# bristol_longshot.net
KiCad netlist of a schematic drawn in EAGLE
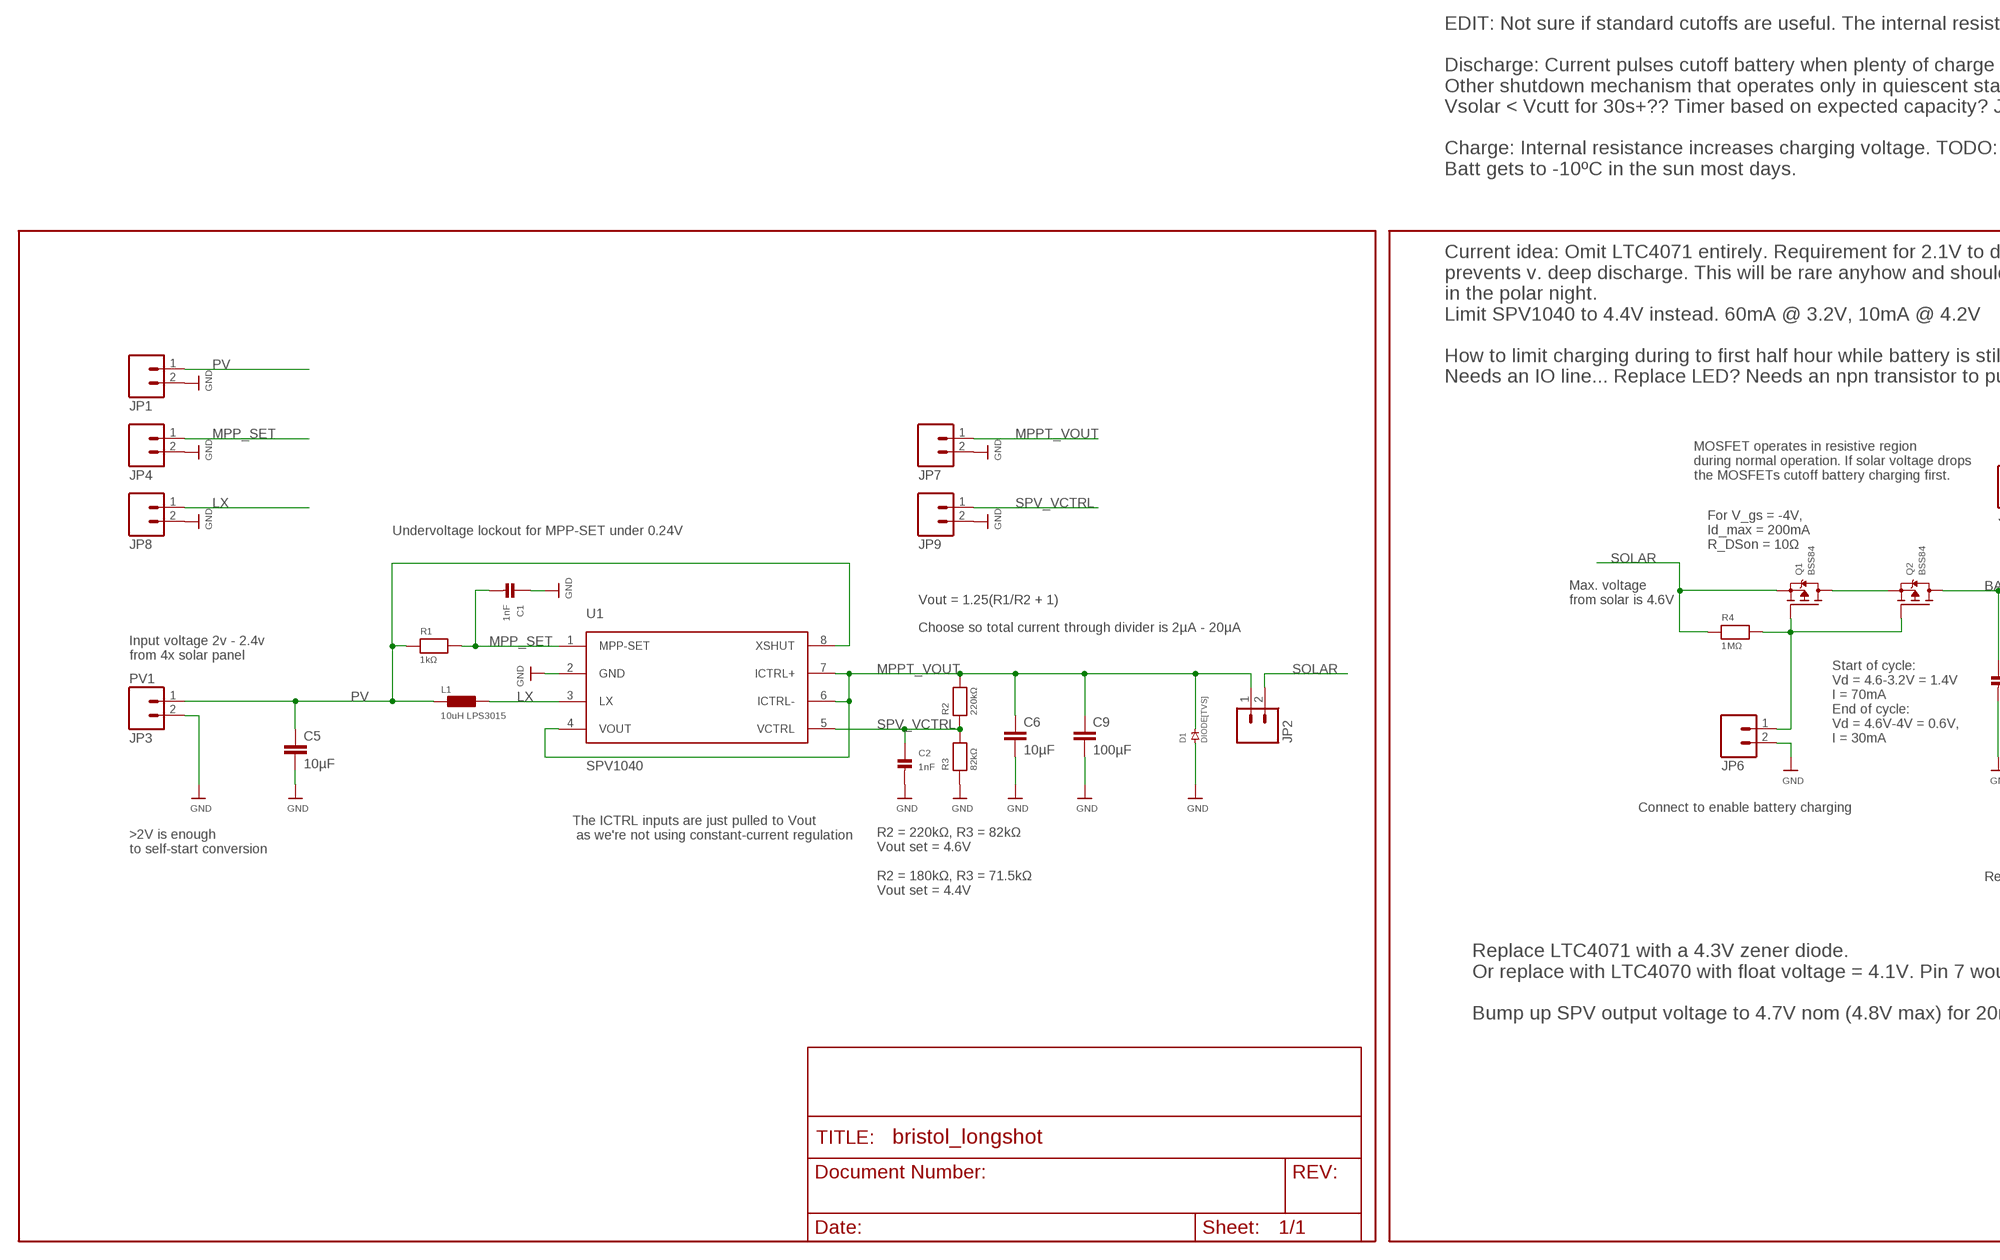
[diagram p0: schematic, sheet 1, part 1 of 2]
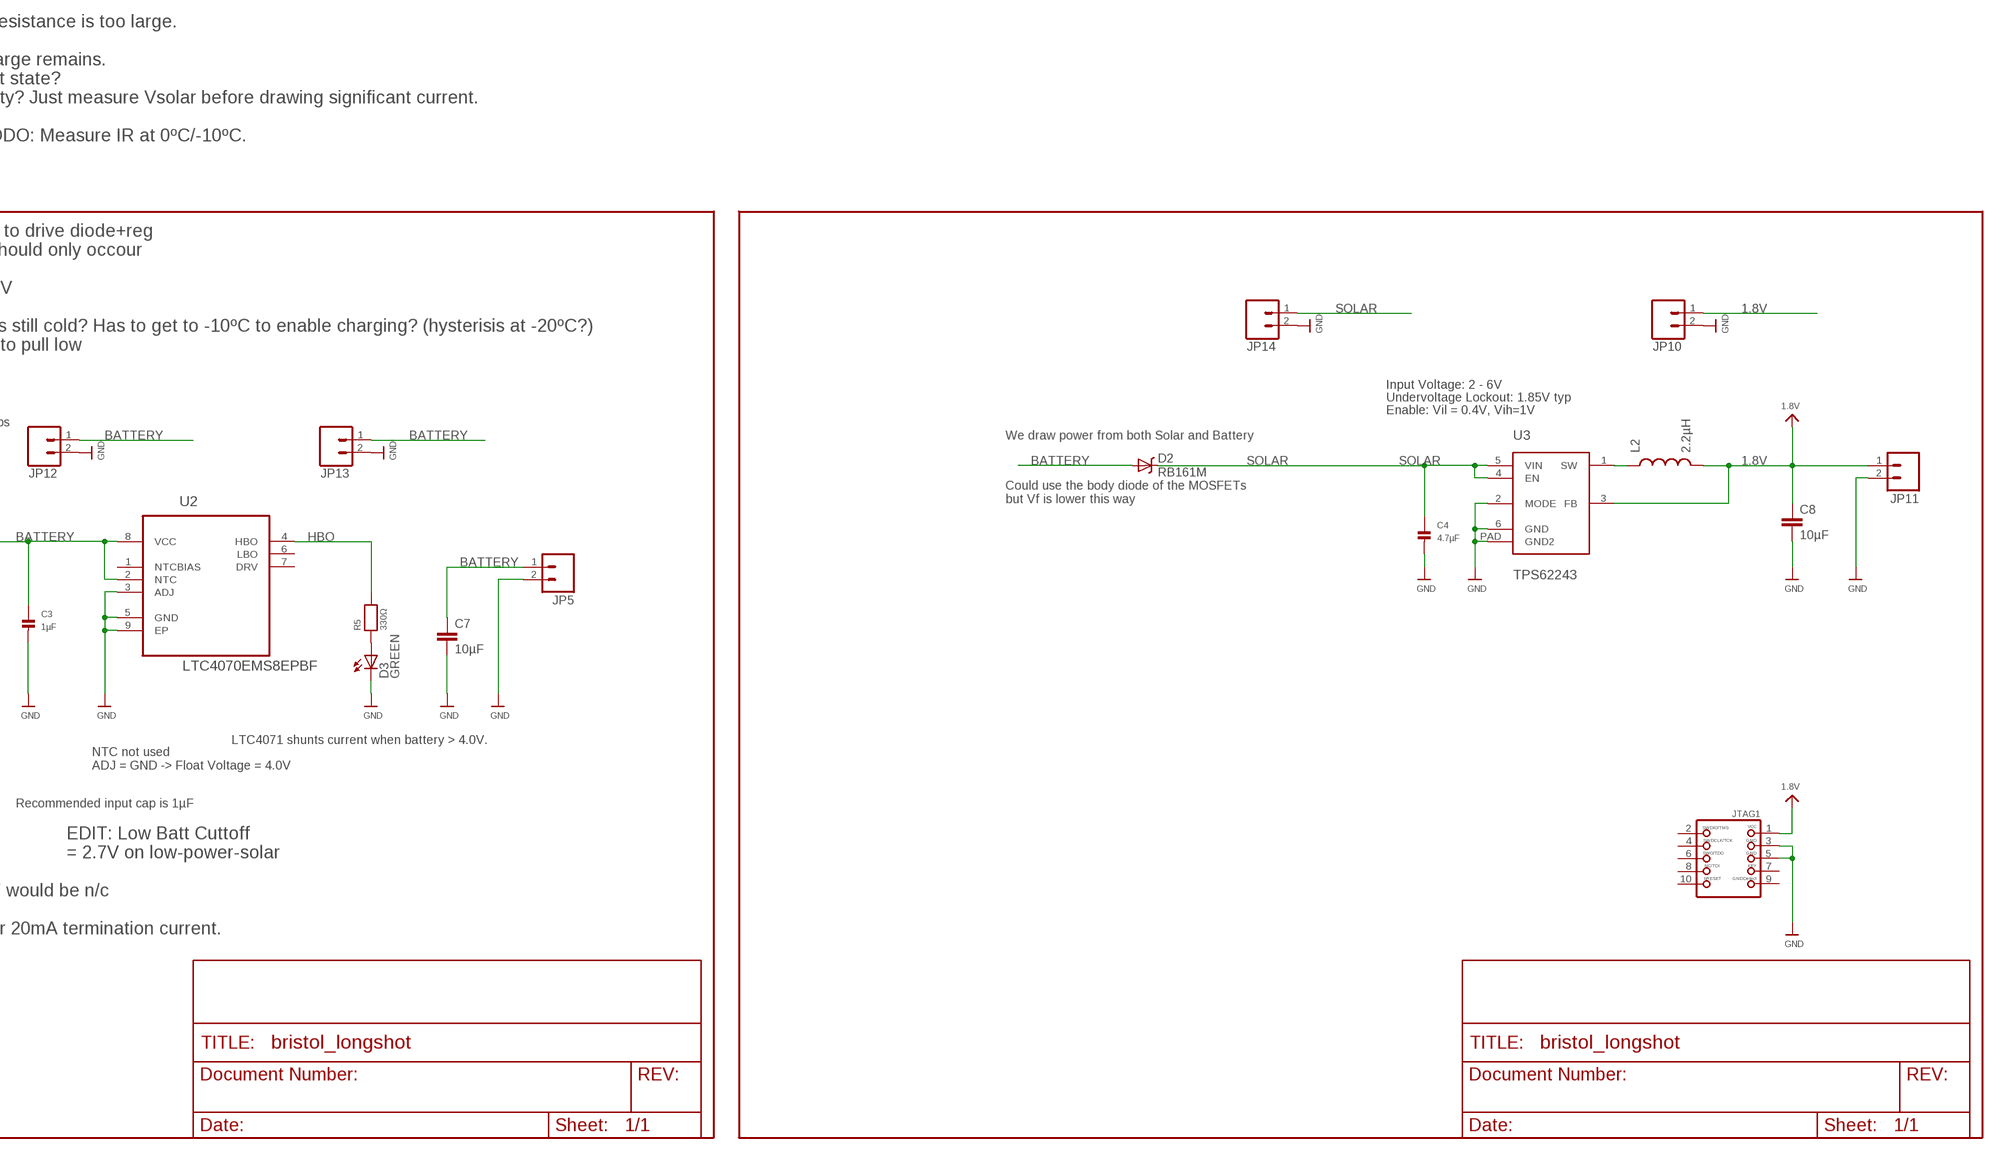
[diagram p1: schematic, sheet 1, part 2 of 2]

(export (version "E")
  (design (tool "Eeschema 10.0.6"))
  (components
    (comp (ref "C1")
      (value "1nF")
      (footprint "eagle-import:_0402@1")
      (libsource (lib "eagle-import") (part "CAP_CERAMIC_0402"))
    )
    (comp (ref "C2")
      (value "1nF")
      (footprint "eagle-import:_0402@1")
      (libsource (lib "eagle-import") (part "CAP_CERAMIC_0402"))
    )
    (comp (ref "C3")
      (value "1µF")
      (footprint "eagle-import:_0402@1")
      (libsource (lib "eagle-import") (part "CAP_CERAMIC_0402"))
    )
    (comp (ref "C4")
      (value "4.7µF")
      (footprint "eagle-import:_0402@1")
      (libsource (lib "eagle-import") (part "CAP_CERAMIC_0402"))
    )
    (comp (ref "C5")
      (value "10µF")
      (footprint "eagle-import:C0603K")
      (libsource (lib "eagle-import") (part "C-EUC0603K"))
    )
    (comp (ref "C6")
      (value "10µF")
      (footprint "eagle-import:C0603K")
      (libsource (lib "eagle-import") (part "C-EUC0603K"))
    )
    (comp (ref "C7")
      (value "10µF")
      (footprint "eagle-import:C0603K")
      (libsource (lib "eagle-import") (part "C-EUC0603K"))
    )
    (comp (ref "C8")
      (value "10µF")
      (footprint "eagle-import:C0603K")
      (libsource (lib "eagle-import") (part "C-EUC0603K"))
    )
    (comp (ref "C9")
      (value "100µF")
      (footprint "eagle-import:C1206K")
      (libsource (lib "eagle-import") (part "C-EUC1206K"))
    )
    (comp (ref "D1")
      (value "DIODE[TVS]")
      (footprint "eagle-import:SOD123W")
      (libsource (lib "eagle-import") (part "DIODE[TVS]"))
    )
    (comp (ref "D2")
      (value "RB161M")
      (footprint "eagle-import:RB161M")
      (libsource (lib "eagle-import") (part "RB161M"))
    )
    (comp (ref "D3")
      (value "GREEN")
      (footprint "eagle-import:CHIPLED_0603")
      (libsource (lib "eagle-import") (part "LEDCHIPLED_0603"))
    )
    (comp (ref "JP1")
      (value "M02LOCK")
      (footprint "eagle-import:1X02_LOCK")
      (libsource (lib "eagle-import") (part "M02LOCK"))
    )
    (comp (ref "JP2")
      (value "M02LOCK")
      (footprint "eagle-import:1X02_LOCK")
      (libsource (lib "eagle-import") (part "M02LOCK"))
    )
    (comp (ref "JP3")
      (value "PV1")
      (footprint "eagle-import:SCREWTERMINAL-3.5MM-2_LOCK")
      (libsource (lib "eagle-import") (part "M023.5MM_LOCK"))
    )
    (comp (ref "JP4")
      (value "M02LOCK")
      (footprint "eagle-import:1X02_LOCK")
      (libsource (lib "eagle-import") (part "M02LOCK"))
    )
    (comp (ref "JP5")
      (value "M023.5MM_LOCK")
      (footprint "eagle-import:SCREWTERMINAL-3.5MM-2_LOCK")
      (libsource (lib "eagle-import") (part "M023.5MM_LOCK"))
    )
    (comp (ref "JP6")
      (value "M02LOCK")
      (footprint "eagle-import:1X02_LOCK")
      (libsource (lib "eagle-import") (part "M02LOCK"))
    )
    (comp (ref "JP7")
      (value "M02LOCK")
      (footprint "eagle-import:1X02_LOCK")
      (libsource (lib "eagle-import") (part "M02LOCK"))
    )
    (comp (ref "JP8")
      (value "M02LOCK")
      (footprint "eagle-import:1X02_LOCK")
      (libsource (lib "eagle-import") (part "M02LOCK"))
    )
    (comp (ref "JP9")
      (value "M02LOCK")
      (footprint "eagle-import:1X02_LOCK")
      (libsource (lib "eagle-import") (part "M02LOCK"))
    )
    (comp (ref "JP10")
      (value "M02LOCK")
      (footprint "eagle-import:1X02_LOCK")
      (libsource (lib "eagle-import") (part "M02LOCK"))
    )
    (comp (ref "JP11")
      (value "M023.5MM_LOCK")
      (footprint "eagle-import:SCREWTERMINAL-3.5MM-2_LOCK")
      (libsource (lib "eagle-import") (part "M023.5MM_LOCK"))
    )
    (comp (ref "JP12")
      (value "M02LOCK")
      (footprint "eagle-import:1X02_LOCK")
      (libsource (lib "eagle-import") (part "M02LOCK"))
    )
    (comp (ref "JP13")
      (value "M02LOCK")
      (footprint "eagle-import:1X02_LOCK")
      (libsource (lib "eagle-import") (part "M02LOCK"))
    )
    (comp (ref "JP14")
      (value "M02LOCK")
      (footprint "eagle-import:1X02_LOCK")
      (libsource (lib "eagle-import") (part "M02LOCK"))
    )
    (comp (ref "JTAG1")
      (value "JTAG-CORTEXM3SMT")
      (footprint "eagle-import:2X05_1.27MM_SMT")
      (libsource (lib "eagle-import") (part "JTAG-CORTEXM3SMT"))
    )
    (comp (ref "L1")
      (value "10uH LPS3015")
      (footprint "eagle-import:LPS3015")
      (libsource (lib "eagle-import") (part "IND-LPS3015"))
    )
    (comp (ref "L2")
      (value "2.2µH")
      (footprint "eagle-import:1007")
      (libsource (lib "eagle-import") (part "INDUCTOR1007"))
    )
    (comp (ref "Q1")
      (value "BSS84")
      (footprint "eagle-import:SOT23")
      (libsource (lib "eagle-import") (part "NX2301P"))
    )
    (comp (ref "Q2")
      (value "BSS84")
      (footprint "eagle-import:SOT23")
      (libsource (lib "eagle-import") (part "NX2301P"))
    )
    (comp (ref "R1")
      (value "1kΩ")
      (footprint "eagle-import:_0402")
      (libsource (lib "eagle-import") (part "RESISTOR_0402"))
    )
    (comp (ref "R2")
      (value "220kΩ")
      (footprint "eagle-import:_0402")
      (libsource (lib "eagle-import") (part "RESISTOR_0402"))
    )
    (comp (ref "R3")
      (value "82kΩ")
      (footprint "eagle-import:_0402")
      (libsource (lib "eagle-import") (part "RESISTOR_0402"))
    )
    (comp (ref "R4")
      (value "1MΩ")
      (footprint "eagle-import:_0402")
      (libsource (lib "eagle-import") (part "RESISTOR_0402"))
    )
    (comp (ref "R5")
      (value "330Ω")
      (footprint "eagle-import:_0402")
      (libsource (lib "eagle-import") (part "RESISTOR_0402"))
    )
    (comp (ref "U1")
      (value "SPV1040")
      (footprint "eagle-import:TSSOP8")
      (libsource (lib "eagle-import") (part "SPV1040"))
    )
    (comp (ref "U2")
      (value "LTC4070EMS8EPBF")
      (footprint "eagle-import:SOP65P490X110-9N")
      (fields (field (name "MPN") "LTC4070EMS8E#PBF"))
      (libsource (lib "eagle-import") (part "LTC4070EMS8EPBF"))
    )
    (comp (ref "U3")
      (value "TPS62243")
      (footprint "eagle-import:S-PWSON-N6")
      (libsource (lib "eagle-import") (part "TPS62243"))
    )
  )
  (nets
    (net (code "1") (name "/BATTERY") (class "Default")
      (node (ref "C3") (pin "1") (pinfunction "P$1_1") (pintype "passive"))
      (node (ref "C7") (pin "1") (pinfunction "1_1") (pintype "passive"))
      (node (ref "D2") (pin "ANODE") (pinfunction "A_ANODE") (pintype "passive"))
      (node (ref "JP12") (pin "1") (pinfunction "1_1") (pintype "passive"))
      (node (ref "JP13") (pin "1") (pinfunction "1_1") (pintype "passive"))
      (node (ref "JP5") (pin "1") (pinfunction "1_1") (pintype "passive"))
      (node (ref "Q2") (pin "3") (pinfunction "D_3") (pintype "passive"))
      (node (ref "U2") (pin "2") (pinfunction "NTC_2") (pintype "input"))
      (node (ref "U2") (pin "8") (pinfunction "VCC_8") (pintype "power_in"))
    )
    (net (code "2") (name "/HBO") (class "Default")
      (node (ref "R5") (pin "2") (pinfunction "2_2") (pintype "passive"))
      (node (ref "U2") (pin "4") (pinfunction "HBO_4") (pintype "output"))
    )
    (net (code "3") (name "/LX") (class "Default")
      (node (ref "JP8") (pin "1") (pinfunction "1_1") (pintype "passive"))
      (node (ref "L1") (pin "2_1") (pinfunction "2_2_1") (pintype "passive"))
      (node (ref "L1") (pin "2_2") (pinfunction "2_2_2") (pintype "passive"))
      (node (ref "L1") (pin "2_3") (pinfunction "2_2_3") (pintype "passive"))
      (node (ref "L1") (pin "2_4") (pinfunction "2_2_4") (pintype "passive"))
      (node (ref "L1") (pin "2_5") (pinfunction "2_2_5") (pintype "passive"))
      (node (ref "L1") (pin "2_6") (pinfunction "2_2_6") (pintype "passive"))
      (node (ref "L1") (pin "2_7") (pinfunction "2_2_7") (pintype "passive"))
      (node (ref "L1") (pin "2_8") (pinfunction "2_2_8") (pintype "passive"))
      (node (ref "L1") (pin "2_9") (pinfunction "2_2_9") (pintype "passive"))
      (node (ref "U1") (pin "3") (pinfunction "LX_3") (pintype "bidirectional"))
    )
    (net (code "4") (name "/MPPT_VOUT") (class "Default")
      (node (ref "C6") (pin "1") (pinfunction "1_1") (pintype "passive"))
      (node (ref "C9") (pin "1") (pinfunction "1_1") (pintype "passive"))
      (node (ref "D1") (pin "P$2") (pinfunction "2_P$2") (pintype "bidirectional"))
      (node (ref "JP2") (pin "1") (pinfunction "1_1") (pintype "passive"))
      (node (ref "JP7") (pin "1") (pinfunction "1_1") (pintype "passive"))
      (node (ref "R2") (pin "2") (pinfunction "2_2") (pintype "passive"))
      (node (ref "U1") (pin "4") (pinfunction "VOUT_4") (pintype "bidirectional"))
      (node (ref "U1") (pin "6") (pinfunction "ICTRL-_6") (pintype "bidirectional"))
      (node (ref "U1") (pin "7") (pinfunction "ICTRL+_7") (pintype "bidirectional"))
    )
    (net (code "5") (name "/MPP_SET") (class "Default")
      (node (ref "C1") (pin "2") (pinfunction "P$2_2") (pintype "passive"))
      (node (ref "JP4") (pin "1") (pinfunction "1_1") (pintype "passive"))
      (node (ref "R1") (pin "2") (pinfunction "2_2") (pintype "passive"))
      (node (ref "U1") (pin "1") (pinfunction "MPP-SET_1") (pintype "bidirectional"))
    )
    (net (code "6") (name "/NTCBIAS") (class "Default")
      (node (ref "U2") (pin "1") (pinfunction "NTCBIAS_1") (pintype "power_in"))
    )
    (net (code "7") (name "/PV") (class "Default")
      (node (ref "C5") (pin "1") (pinfunction "1_1") (pintype "passive"))
      (node (ref "JP1") (pin "1") (pinfunction "1_1") (pintype "passive"))
      (node (ref "JP3") (pin "1") (pinfunction "1_1") (pintype "passive"))
      (node (ref "L1") (pin "1_1") (pinfunction "1_1_1") (pintype "passive"))
      (node (ref "L1") (pin "1_2") (pinfunction "1_1_2") (pintype "passive"))
      (node (ref "L1") (pin "1_3") (pinfunction "1_1_3") (pintype "passive"))
      (node (ref "L1") (pin "1_4") (pinfunction "1_1_4") (pintype "passive"))
      (node (ref "L1") (pin "1_5") (pinfunction "1_1_5") (pintype "passive"))
      (node (ref "L1") (pin "1_6") (pinfunction "1_1_6") (pintype "passive"))
      (node (ref "L1") (pin "1_7") (pinfunction "1_1_7") (pintype "passive"))
      (node (ref "L1") (pin "1_8") (pinfunction "1_1_8") (pintype "passive"))
      (node (ref "L1") (pin "1_9") (pinfunction "1_1_9") (pintype "passive"))
      (node (ref "R1") (pin "1") (pinfunction "1_1") (pintype "passive"))
      (node (ref "U1") (pin "8") (pinfunction "XSHUT_8") (pintype "bidirectional"))
    )
    (net (code "8") (name "/SOLAR") (class "Default")
      (node (ref "C4") (pin "1") (pinfunction "P$1_1") (pintype "passive"))
      (node (ref "D2") (pin "CATHODE") (pinfunction "C_CATHODE") (pintype "passive"))
      (node (ref "JP14") (pin "1") (pinfunction "1_1") (pintype "passive"))
      (node (ref "JP2") (pin "2") (pinfunction "2_2") (pintype "passive"))
      (node (ref "Q1") (pin "2") (pinfunction "S_2") (pintype "passive"))
      (node (ref "R4") (pin "1") (pinfunction "1_1") (pintype "passive"))
      (node (ref "U3") (pin "4") (pinfunction "EN_4") (pintype "bidirectional"))
      (node (ref "U3") (pin "5") (pinfunction "VIN_5") (pintype "bidirectional"))
    )
    (net (code "9") (name "/SPV_VCTRL") (class "Default")
      (node (ref "C2") (pin "1") (pinfunction "P$1_1") (pintype "passive"))
      (node (ref "JP9") (pin "1") (pinfunction "1_1") (pintype "passive"))
      (node (ref "R2") (pin "1") (pinfunction "1_1") (pintype "passive"))
      (node (ref "R3") (pin "2") (pinfunction "2_2") (pintype "passive"))
      (node (ref "U1") (pin "5") (pinfunction "VCTRL_5") (pintype "bidirectional"))
    )
    (net (code "10") (name "1.8V") (class "Default")
      (node (ref "C8") (pin "1") (pinfunction "1_1") (pintype "passive"))
      (node (ref "JP10") (pin "1") (pinfunction "1_1") (pintype "passive"))
      (node (ref "JP11") (pin "1") (pinfunction "1_1") (pintype "passive"))
      (node (ref "JTAG1") (pin "1") (pinfunction "1_1") (pintype "passive"))
      (node (ref "L2") (pin "2") (pinfunction "2_2") (pintype "passive"))
      (node (ref "U3") (pin "3") (pinfunction "FB_3") (pintype "bidirectional"))
    )
    (net (code "11") (name "GND") (class "Default")
      (node (ref "C1") (pin "1") (pinfunction "P$1_1") (pintype "passive"))
      (node (ref "C2") (pin "2") (pinfunction "P$2_2") (pintype "passive"))
      (node (ref "C3") (pin "2") (pinfunction "P$2_2") (pintype "passive"))
      (node (ref "C4") (pin "2") (pinfunction "P$2_2") (pintype "passive"))
      (node (ref "C5") (pin "2") (pinfunction "2_2") (pintype "passive"))
      (node (ref "C6") (pin "2") (pinfunction "2_2") (pintype "passive"))
      (node (ref "C7") (pin "2") (pinfunction "2_2") (pintype "passive"))
      (node (ref "C8") (pin "2") (pinfunction "2_2") (pintype "passive"))
      (node (ref "C9") (pin "2") (pinfunction "2_2") (pintype "passive"))
      (node (ref "D1") (pin "P$1") (pinfunction "1_P$1") (pintype "bidirectional"))
      (node (ref "D3") (pin "C") (pinfunction "C_C") (pintype "passive"))
      (node (ref "JP1") (pin "2") (pinfunction "2_2") (pintype "passive"))
      (node (ref "JP10") (pin "2") (pinfunction "2_2") (pintype "passive"))
      (node (ref "JP11") (pin "2") (pinfunction "2_2") (pintype "passive"))
      (node (ref "JP12") (pin "2") (pinfunction "2_2") (pintype "passive"))
      (node (ref "JP13") (pin "2") (pinfunction "2_2") (pintype "passive"))
      (node (ref "JP14") (pin "2") (pinfunction "2_2") (pintype "passive"))
      (node (ref "JP3") (pin "2") (pinfunction "2_2") (pintype "passive"))
      (node (ref "JP4") (pin "2") (pinfunction "2_2") (pintype "passive"))
      (node (ref "JP5") (pin "2") (pinfunction "2_2") (pintype "passive"))
      (node (ref "JP6") (pin "2") (pinfunction "2_2") (pintype "passive"))
      (node (ref "JP7") (pin "2") (pinfunction "2_2") (pintype "passive"))
      (node (ref "JP8") (pin "2") (pinfunction "2_2") (pintype "passive"))
      (node (ref "JP9") (pin "2") (pinfunction "2_2") (pintype "passive"))
      (node (ref "JTAG1") (pin "3") (pinfunction "3_3") (pintype "passive"))
      (node (ref "JTAG1") (pin "5") (pinfunction "5_5") (pintype "passive"))
      (node (ref "R3") (pin "1") (pinfunction "1_1") (pintype "passive"))
      (node (ref "U1") (pin "2") (pinfunction "GND_2") (pintype "power_in"))
      (node (ref "U2") (pin "3") (pinfunction "ADJ_3") (pintype "input"))
      (node (ref "U2") (pin "5") (pinfunction "GND_5") (pintype "passive"))
      (node (ref "U2") (pin "9") (pinfunction "EP_9") (pintype "passive"))
      (node (ref "U3") (pin "2") (pinfunction "MODE_2") (pintype "bidirectional"))
      (node (ref "U3") (pin "6") (pinfunction "GND_6") (pintype "bidirectional"))
      (node (ref "U3") (pin "PAD") (pinfunction "GND2_PAD") (pintype "bidirectional"))
    )
    (net (code "12") (name "Net-(D3-PadA)") (class "Default")
      (node (ref "D3") (pin "A") (pinfunction "A_A") (pintype "passive"))
      (node (ref "R5") (pin "1") (pinfunction "1_1") (pintype "passive"))
    )
    (net (code "13") (name "Net-(Q1-D)") (class "Default")
      (node (ref "Q1") (pin "3") (pinfunction "D_3") (pintype "passive"))
      (node (ref "Q2") (pin "2") (pinfunction "S_2") (pintype "passive"))
    )
    (net (code "14") (name "Net-(Q1-G)") (class "Default")
      (node (ref "JP6") (pin "1") (pinfunction "1_1") (pintype "passive"))
      (node (ref "Q1") (pin "1") (pinfunction "G_1") (pintype "passive"))
      (node (ref "Q2") (pin "1") (pinfunction "G_1") (pintype "passive"))
      (node (ref "R4") (pin "2") (pinfunction "2_2") (pintype "passive"))
    )
    (net (code "15") (name "Net-(U3-SW)") (class "Default")
      (node (ref "L2") (pin "1") (pinfunction "1_1") (pintype "passive"))
      (node (ref "U3") (pin "1") (pinfunction "SW_1") (pintype "bidirectional"))
    )
    (net (code "16") (name "unconnected-(JTAG1-Pad2)") (class "Default")
      (node (ref "JTAG1") (pin "2") (pinfunction "2_2") (pintype "passive"))
    )
    (net (code "17") (name "unconnected-(JTAG1-Pad4)") (class "Default")
      (node (ref "JTAG1") (pin "4") (pinfunction "4_4") (pintype "passive"))
    )
    (net (code "18") (name "unconnected-(JTAG1-Pad6)") (class "Default")
      (node (ref "JTAG1") (pin "6") (pinfunction "6_6") (pintype "passive"))
    )
    (net (code "19") (name "unconnected-(JTAG1-Pad7)") (class "Default")
      (node (ref "JTAG1") (pin "7") (pinfunction "7_7") (pintype "passive"))
    )
    (net (code "20") (name "unconnected-(JTAG1-Pad8)") (class "Default")
      (node (ref "JTAG1") (pin "8") (pinfunction "8_8") (pintype "passive"))
    )
    (net (code "21") (name "unconnected-(JTAG1-Pad9)") (class "Default")
      (node (ref "JTAG1") (pin "9") (pinfunction "9_9") (pintype "passive"))
    )
    (net (code "22") (name "unconnected-(JTAG1-Pad10)") (class "Default")
      (node (ref "JTAG1") (pin "10") (pinfunction "10_10") (pintype "passive"))
    )
    (net (code "23") (name "unconnected-(U2-DRV-Pad7)") (class "Default")
      (node (ref "U2") (pin "7") (pinfunction "DRV_7") (pintype "output"))
    )
    (net (code "24") (name "unconnected-(U2-LBO-Pad6)") (class "Default")
      (node (ref "U2") (pin "6") (pinfunction "LBO_6") (pintype "output"))
    )
  )
)
